# SCH_Usbhub_easyeda_file.net
KiCad netlist of a schematic drawn in EasyEDA
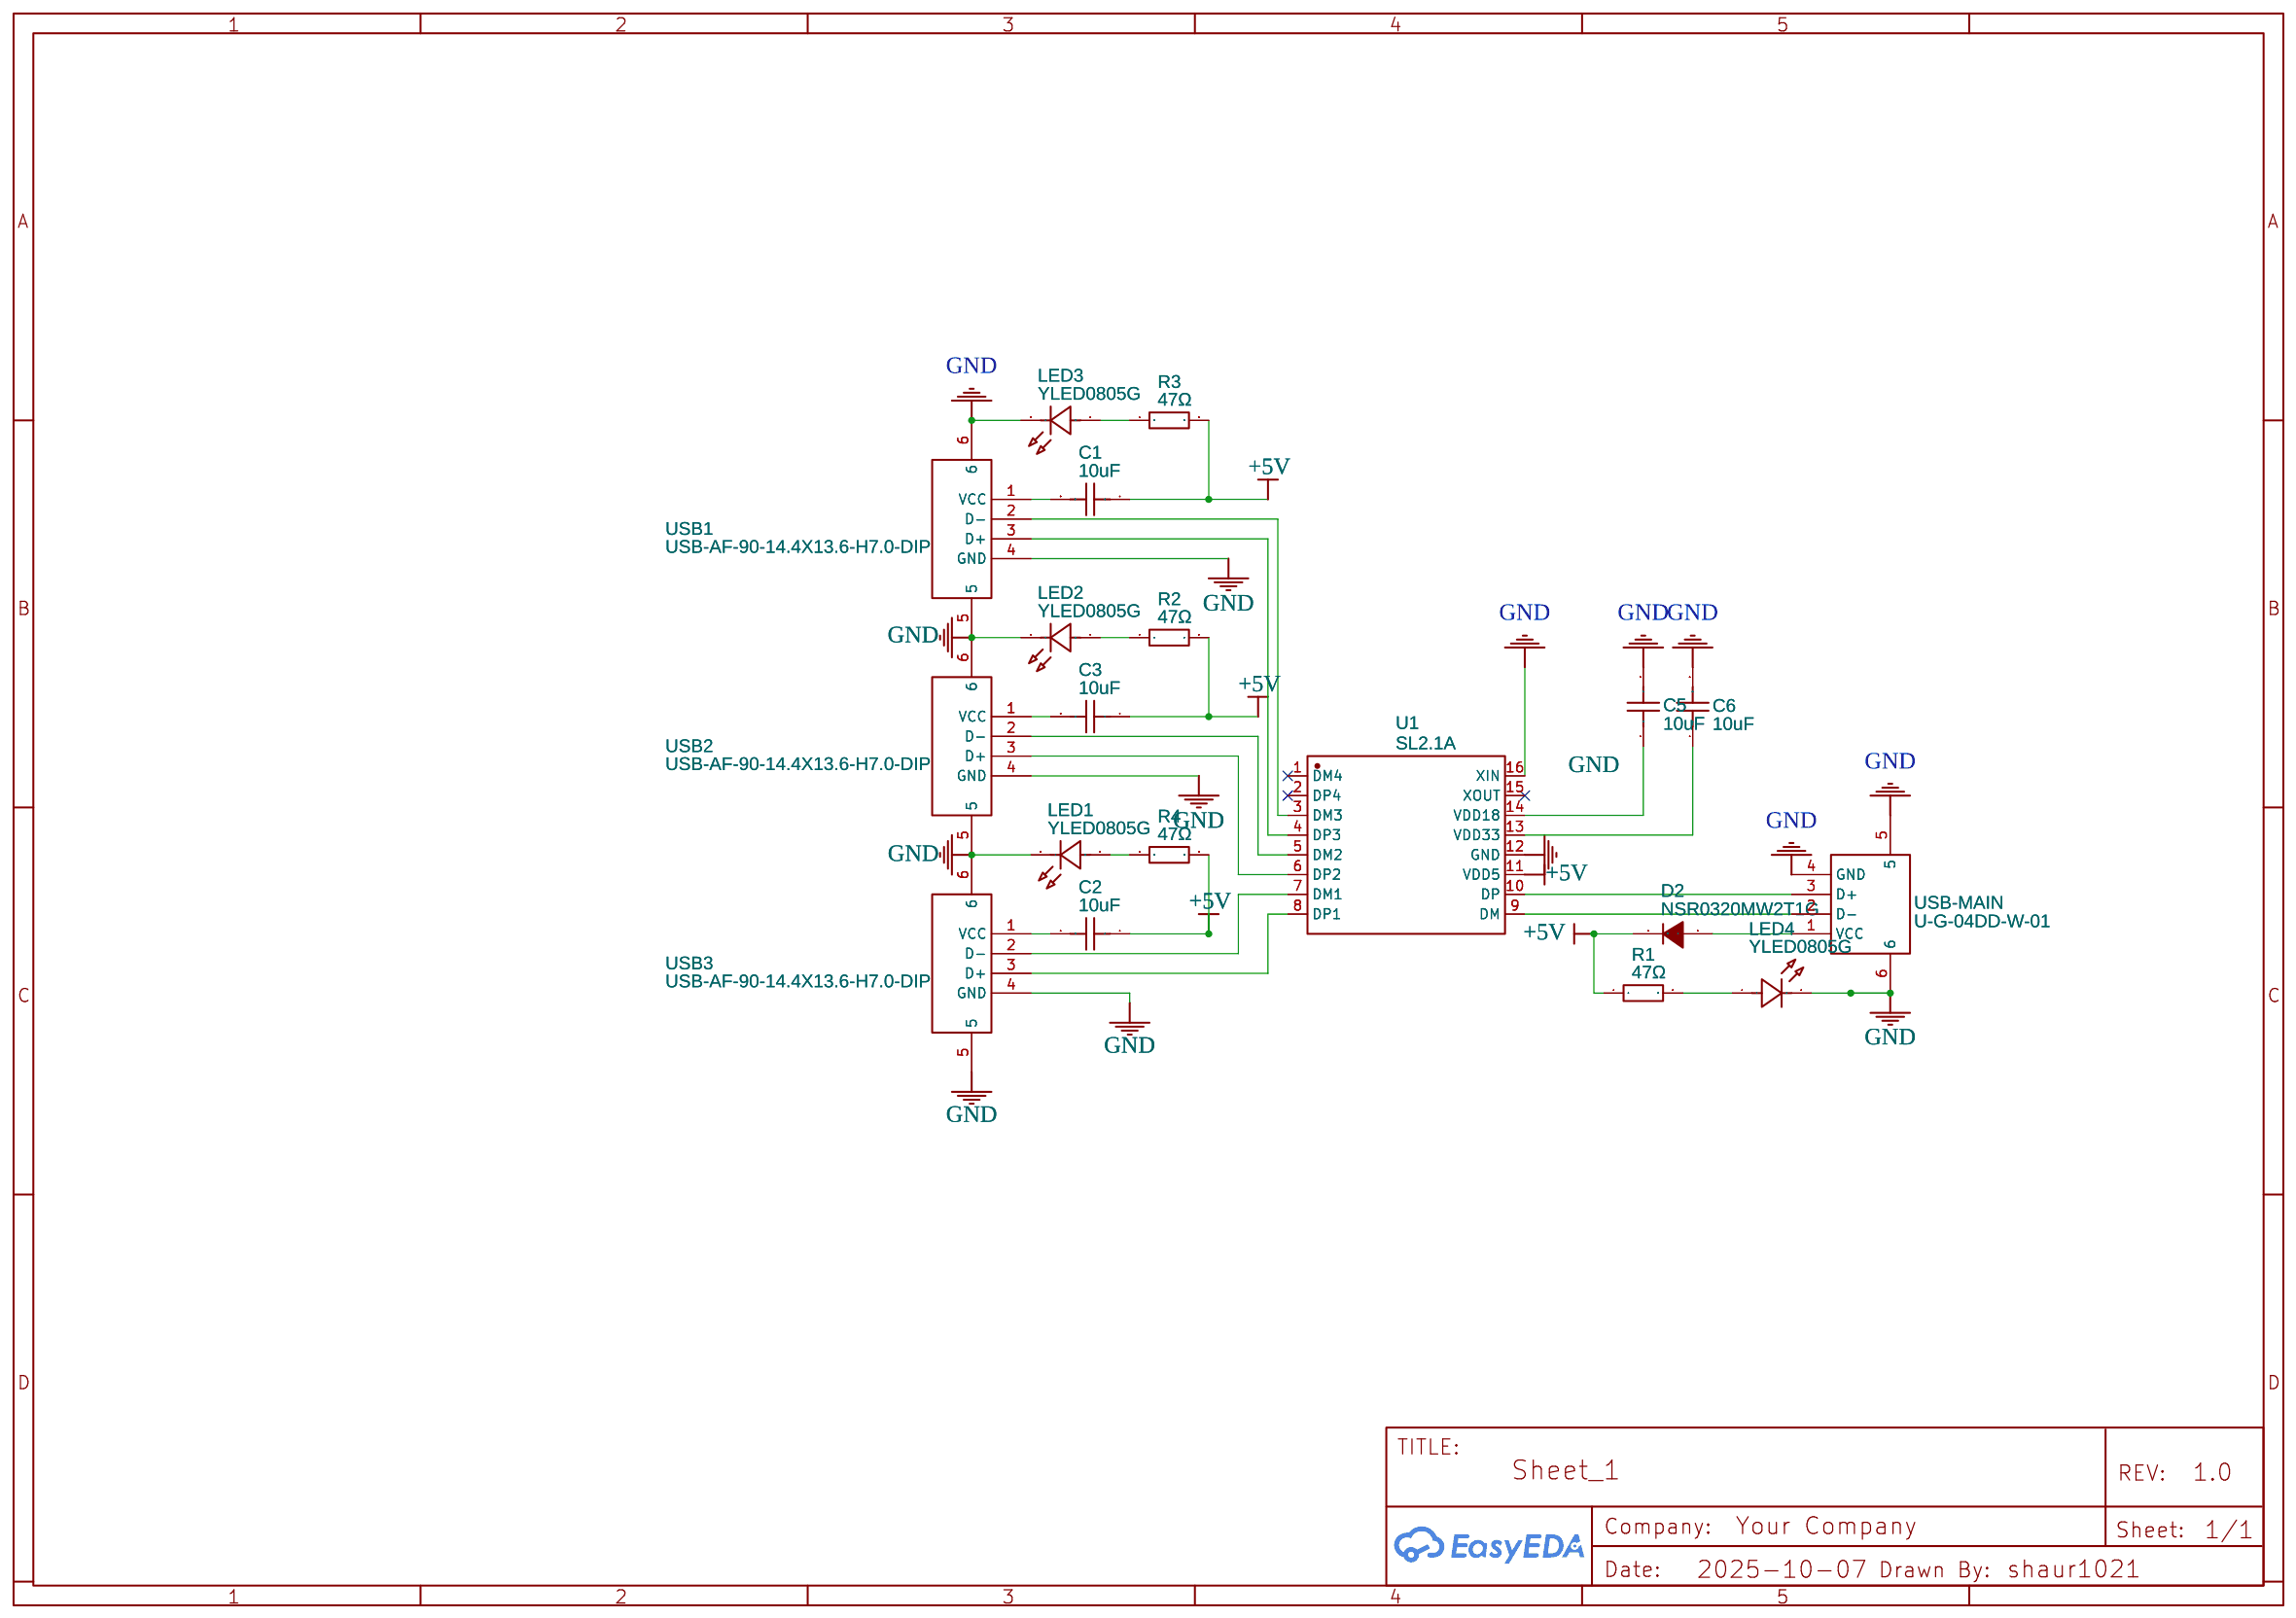
[diagram p0: schematic sheet]

(export (version "E")
  (design (tool "Eeschema 10.0.6"))
  (components
    (comp (ref "C1")
      (value "10uF")
      (fields
        (field (name "Manufacturer Part") "CL10A106KP8NNNC")
        (field (name "Manufacturer") "SAMSUNG(三星)")
      )
      (libsource (lib "") (part "CL10A106KP8NNNC"))
    )
    (comp (ref "C2")
      (value "10uF")
      (fields
        (field (name "Manufacturer Part") "CL10A106KP8NNNC")
        (field (name "Manufacturer") "SAMSUNG(三星)")
      )
      (libsource (lib "") (part "CL10A106KP8NNNC"))
    )
    (comp (ref "C3")
      (value "10uF")
      (fields
        (field (name "Manufacturer Part") "CL10A106KP8NNNC")
        (field (name "Manufacturer") "SAMSUNG(三星)")
      )
      (libsource (lib "") (part "CL10A106KP8NNNC"))
    )
    (comp (ref "C5")
      (value "10uF")
      (fields
        (field (name "Manufacturer Part") "CL10A106KP8NNNC")
        (field (name "Manufacturer") "SAMSUNG(三星)")
      )
      (libsource (lib "") (part "CL10A106KP8NNNC_1"))
    )
    (comp (ref "C6")
      (value "10uF")
      (fields
        (field (name "Manufacturer Part") "CL10A106KP8NNNC")
        (field (name "Manufacturer") "SAMSUNG(三星)")
      )
      (libsource (lib "") (part "CL10A106KP8NNNC_1"))
    )
    (comp (ref "D2")
      (value "NSR0320MW2T1G")
      (fields (field (name "Manufacturer") "onsemi(安森美)"))
      (libsource (lib "") (part "NSR0320MW2T1G"))
    )
    (comp (ref "LED1")
      (value "YLED0805G")
      (fields (field (name "Manufacturer") "YONGYUTAI(永裕泰)"))
      (libsource (lib "") (part "YLED0805G"))
    )
    (comp (ref "LED2")
      (value "YLED0805G")
      (fields (field (name "Manufacturer") "YONGYUTAI(永裕泰)"))
      (libsource (lib "") (part "YLED0805G"))
    )
    (comp (ref "LED3")
      (value "YLED0805G")
      (fields (field (name "Manufacturer") "YONGYUTAI(永裕泰)"))
      (libsource (lib "") (part "YLED0805G"))
    )
    (comp (ref "LED4")
      (value "YLED0805G")
      (fields (field (name "Manufacturer") "YONGYUTAI(永裕泰)"))
      (libsource (lib "") (part "YLED0805G_1"))
    )
    (comp (ref "R1")
      (value "47Ω")
      (fields
        (field (name "Manufacturer Part") "0603WAF470JT5E")
        (field (name "Manufacturer") "UNI-ROYAL(厚声)")
      )
      (libsource (lib "") (part "0603WAF470JT5E"))
    )
    (comp (ref "R2")
      (value "47Ω")
      (fields
        (field (name "Manufacturer Part") "0603WAF470JT5E")
        (field (name "Manufacturer") "UNI-ROYAL(厚声)")
      )
      (libsource (lib "") (part "0603WAF470JT5E"))
    )
    (comp (ref "R3")
      (value "47Ω")
      (fields
        (field (name "Manufacturer Part") "0603WAF470JT5E")
        (field (name "Manufacturer") "UNI-ROYAL(厚声)")
      )
      (libsource (lib "") (part "0603WAF470JT5E"))
    )
    (comp (ref "R4")
      (value "47Ω")
      (fields
        (field (name "Manufacturer Part") "0603WAF470JT5E")
        (field (name "Manufacturer") "UNI-ROYAL(厚声)")
      )
      (libsource (lib "") (part "0603WAF470JT5E"))
    )
    (comp (ref "U1")
      (value "SL2.1A")
      (fields (field (name "Manufacturer") "CoreChips(和芯润德)"))
      (libsource (lib "") (part "SL2.1A"))
    )
    (comp (ref "USB-MAIN")
      (value "U-G-04DD-W-01")
      (fields (field (name "Manufacturer Part") "U-G-O4DD-W-1") (field (name "Manufacturer") "韩国韩荣"))
      (libsource (lib "") (part "U-G-04DD-W-01"))
    )
    (comp (ref "USB1")
      (value "USB-AF-90-14.4X13.6-H7.0-DIP")
      (fields (field (name "Manufacturer Part") "903-131A1011D10100") (field (name "Manufacturer") "精拓金"))
      (libsource (lib "") (part "USB-AF-90-14.4X13.6-H7.0-DIP"))
    )
    (comp (ref "USB2")
      (value "USB-AF-90-14.4X13.6-H7.0-DIP")
      (fields (field (name "Manufacturer Part") "903-131A1011D10100") (field (name "Manufacturer") "精拓金"))
      (libsource (lib "") (part "USB-AF-90-14.4X13.6-H7.0-DIP"))
    )
    (comp (ref "USB3")
      (value "USB-AF-90-14.4X13.6-H7.0-DIP")
      (fields (field (name "Manufacturer Part") "903-131A1011D10100") (field (name "Manufacturer") "精拓金"))
      (libsource (lib "") (part "USB-AF-90-14.4X13.6-H7.0-DIP"))
    )
  )
  (nets
    (net (code "1") (name "+5V") (class "Default")
      (node (ref "C1") (pin "1") (pinfunction "1_1") (pintype "unspecified"))
      (node (ref "C2") (pin "1") (pinfunction "1_1") (pintype "unspecified"))
      (node (ref "C3") (pin "1") (pinfunction "1_1") (pintype "unspecified"))
      (node (ref "D2") (pin "1") (pinfunction "C_1") (pintype "unspecified"))
      (node (ref "R1") (pin "1") (pinfunction "1_1") (pintype "input"))
      (node (ref "R2") (pin "2") (pinfunction "2_2") (pintype "input"))
      (node (ref "R3") (pin "2") (pinfunction "2_2") (pintype "input"))
      (node (ref "R4") (pin "2") (pinfunction "2_2") (pintype "input"))
      (node (ref "U1") (pin "11") (pinfunction "VDD5_11") (pintype "unspecified"))
    )
    (net (code "2") (name "GND") (class "Default")
      (node (ref "C5") (pin "2") (pinfunction "2_2") (pintype "unspecified"))
      (node (ref "C6") (pin "2") (pinfunction "2_2") (pintype "unspecified"))
      (node (ref "LED1") (pin "2") (pinfunction "K_2") (pintype "unspecified"))
      (node (ref "LED2") (pin "2") (pinfunction "K_2") (pintype "unspecified"))
      (node (ref "LED3") (pin "2") (pinfunction "K_2") (pintype "unspecified"))
      (node (ref "LED4") (pin "2") (pinfunction "K_2") (pintype "unspecified"))
      (node (ref "U1") (pin "12") (pinfunction "GND_12") (pintype "unspecified"))
      (node (ref "U1") (pin "16") (pinfunction "XIN_16") (pintype "unspecified"))
      (node (ref "USB-MAIN") (pin "4") (pinfunction "GND_4") (pintype "unspecified"))
      (node (ref "USB-MAIN") (pin "5") (pinfunction "5_5") (pintype "unspecified"))
      (node (ref "USB-MAIN") (pin "6") (pinfunction "6_6") (pintype "unspecified"))
      (node (ref "USB1") (pin "4") (pinfunction "GND_4") (pintype "unspecified"))
      (node (ref "USB1") (pin "5") (pinfunction "5_5") (pintype "unspecified"))
      (node (ref "USB1") (pin "6") (pinfunction "6_6") (pintype "unspecified"))
      (node (ref "USB2") (pin "4") (pinfunction "GND_4") (pintype "unspecified"))
      (node (ref "USB2") (pin "5") (pinfunction "5_5") (pintype "unspecified"))
      (node (ref "USB2") (pin "6") (pinfunction "6_6") (pintype "unspecified"))
      (node (ref "USB3") (pin "4") (pinfunction "GND_4") (pintype "unspecified"))
      (node (ref "USB3") (pin "5") (pinfunction "5_5") (pintype "unspecified"))
      (node (ref "USB3") (pin "6") (pinfunction "6_6") (pintype "unspecified"))
    )
    (net (code "3") (name "Net-(D2-A)") (class "Default")
      (node (ref "D2") (pin "2") (pinfunction "A_2") (pintype "unspecified"))
      (node (ref "USB-MAIN") (pin "1") (pinfunction "VCC_1") (pintype "unspecified"))
    )
    (net (code "4") (name "Net-(LED1-A)") (class "Default")
      (node (ref "LED1") (pin "1") (pinfunction "A_1") (pintype "unspecified"))
      (node (ref "R4") (pin "1") (pinfunction "1_1") (pintype "input"))
    )
    (net (code "5") (name "Net-(LED2-A)") (class "Default")
      (node (ref "LED2") (pin "1") (pinfunction "A_1") (pintype "unspecified"))
      (node (ref "R2") (pin "1") (pinfunction "1_1") (pintype "input"))
    )
    (net (code "6") (name "Net-(LED3-A)") (class "Default")
      (node (ref "LED3") (pin "1") (pinfunction "A_1") (pintype "unspecified"))
      (node (ref "R3") (pin "1") (pinfunction "1_1") (pintype "input"))
    )
    (net (code "7") (name "Net-(LED4-A)") (class "Default")
      (node (ref "LED4") (pin "1") (pinfunction "A_1") (pintype "unspecified"))
      (node (ref "R1") (pin "2") (pinfunction "2_2") (pintype "input"))
    )
    (net (code "8") (name "Net-(U1-DM)") (class "Default")
      (node (ref "U1") (pin "9") (pinfunction "DM_9") (pintype "unspecified"))
      (node (ref "USB-MAIN") (pin "2") (pinfunction "D-_2") (pintype "unspecified"))
    )
    (net (code "9") (name "Net-(U1-DM1)") (class "Default")
      (node (ref "U1") (pin "7") (pinfunction "DM1_7") (pintype "unspecified"))
      (node (ref "USB3") (pin "2") (pinfunction "D-_2") (pintype "unspecified"))
    )
    (net (code "10") (name "Net-(U1-DM2)") (class "Default")
      (node (ref "U1") (pin "5") (pinfunction "DM2_5") (pintype "unspecified"))
      (node (ref "USB2") (pin "2") (pinfunction "D-_2") (pintype "unspecified"))
    )
    (net (code "11") (name "Net-(U1-DM3)") (class "Default")
      (node (ref "U1") (pin "3") (pinfunction "DM3_3") (pintype "unspecified"))
      (node (ref "USB1") (pin "2") (pinfunction "D-_2") (pintype "unspecified"))
    )
    (net (code "12") (name "Net-(U1-DP)") (class "Default")
      (node (ref "U1") (pin "10") (pinfunction "DP_10") (pintype "unspecified"))
      (node (ref "USB-MAIN") (pin "3") (pinfunction "D+_3") (pintype "unspecified"))
    )
    (net (code "13") (name "Net-(U1-DP1)") (class "Default")
      (node (ref "U1") (pin "8") (pinfunction "DP1_8") (pintype "unspecified"))
      (node (ref "USB3") (pin "3") (pinfunction "D+_3") (pintype "unspecified"))
    )
    (net (code "14") (name "Net-(U1-DP2)") (class "Default")
      (node (ref "U1") (pin "6") (pinfunction "DP2_6") (pintype "unspecified"))
      (node (ref "USB2") (pin "3") (pinfunction "D+_3") (pintype "unspecified"))
    )
    (net (code "15") (name "Net-(U1-DP3)") (class "Default")
      (node (ref "U1") (pin "4") (pinfunction "DP3_4") (pintype "unspecified"))
      (node (ref "USB1") (pin "3") (pinfunction "D+_3") (pintype "unspecified"))
    )
    (net (code "16") (name "Net-(U1-VDD18)") (class "Default")
      (node (ref "C5") (pin "1") (pinfunction "1_1") (pintype "unspecified"))
      (node (ref "U1") (pin "14") (pinfunction "VDD18_14") (pintype "unspecified"))
    )
    (net (code "17") (name "Net-(U1-VDD33)") (class "Default")
      (node (ref "C6") (pin "1") (pinfunction "1_1") (pintype "unspecified"))
      (node (ref "U1") (pin "13") (pinfunction "VDD33_13") (pintype "unspecified"))
    )
    (net (code "18") (name "Net-(USB1-VCC)") (class "Default")
      (node (ref "C1") (pin "2") (pinfunction "2_2") (pintype "unspecified"))
      (node (ref "USB1") (pin "1") (pinfunction "VCC_1") (pintype "unspecified"))
    )
    (net (code "19") (name "Net-(USB2-VCC)") (class "Default")
      (node (ref "C3") (pin "2") (pinfunction "2_2") (pintype "unspecified"))
      (node (ref "USB2") (pin "1") (pinfunction "VCC_1") (pintype "unspecified"))
    )
    (net (code "20") (name "Net-(USB3-VCC)") (class "Default")
      (node (ref "C2") (pin "2") (pinfunction "2_2") (pintype "unspecified"))
      (node (ref "USB3") (pin "1") (pinfunction "VCC_1") (pintype "unspecified"))
    )
    (net (code "21") (name "unconnected-(U1-DM4-Pad1)") (class "Default")
      (node (ref "U1") (pin "1") (pinfunction "DM4_1") (pintype "unspecified+no_connect"))
    )
    (net (code "22") (name "unconnected-(U1-DP4-Pad2)") (class "Default")
      (node (ref "U1") (pin "2") (pinfunction "DP4_2") (pintype "unspecified+no_connect"))
    )
    (net (code "23") (name "unconnected-(U1-XOUT-Pad15)") (class "Default")
      (node (ref "U1") (pin "15") (pinfunction "XOUT_15") (pintype "unspecified+no_connect"))
    )
  )
)
